# PSU_LM2704_16V5.net
KiCad netlist of a schematic drawn in Altium Designer
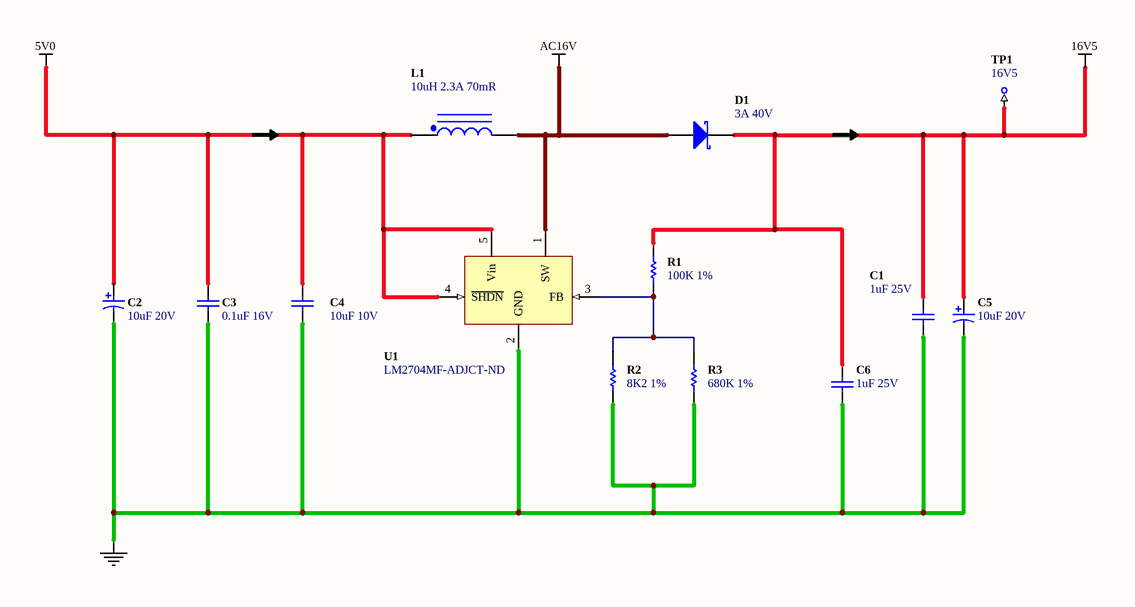
[diagram p0: PSU_LM2704_16V5.SchDoc]

(export (version "E")
  (design (tool "Eeschema 10.0.6"))
  (components
    (comp (ref "C1")
      (value "1uF 25V")
      (footprint "CAPC3216-STAR")
      (description "Capacitor, Ceramic, 1uF 10% 25V 1206 (3216) X7R")
      (fields (field (name "TOLERANCE") "10 %"))
      (libsource (lib "altium-import") (part "root_2_CAP-NP_"))
    )
    (comp (ref "C2")
      (value "10uF 20V")
      (footprint "CAPC3528-STAR")
      (description "Capacitor, Tantalum, 10uF 10% 20V MCCT-B (3528)")
      (fields (field (name "TOLERANCE") "10 %"))
      (libsource (lib "altium-import") (part "root_0_CAP-P_"))
    )
    (comp (ref "C3")
      (value "0.1uF 16V")
      (footprint "CAPC1005-STAR")
      (description "Capacitor, Ceramic, 0.1uF 10% 16V 0402 (1005) X7R")
      (fields (field (name "TOLERANCE") "10 %"))
      (libsource (lib "altium-import") (part "root_0_CAP-NP_"))
    )
    (comp (ref "C4")
      (value "10uF 10V")
      (footprint "CAPC2012-STAR")
      (description "Capacitor, Ceramic, 10uF 10% 10V 0805 (2012) X5R")
      (fields (field (name "TOLERANCE") "10 %"))
      (libsource (lib "altium-import") (part "root_2_CAP-NP_"))
    )
    (comp (ref "C5")
      (value "10uF 20V")
      (footprint "CAPC3528-STAR")
      (description "Capacitor, Tantalum, 10uF 10% 20V MCCT-B (3528)")
      (fields (field (name "TOLERANCE") "10 %"))
      (libsource (lib "altium-import") (part "root_0_CAP-P_"))
    )
    (comp (ref "C6")
      (value "1uF 25V")
      (footprint "CAPC3216-STAR")
      (description "Capacitor, Ceramic, 1uF 10% 25V 1206 (3216) X7R")
      (fields (field (name "TOLERANCE") "10 %"))
      (libsource (lib "altium-import") (part "root_2_CAP-NP_"))
    )
    (comp (ref "D1")
      (value "3A 40V")
      (footprint "DIOM5027")
      (description "Schottky Diode, 3A 40V")
      (libsource (lib "altium-import") (part "root_0_DIO-SCHOTTKY-1S_"))
    )
    (comp (ref "L1")
      (value "10uH 2.3A 70mR")
      (footprint "INDP7575")
      (description "Inductor, Magnetic Core 10uH 2.3A 70mR INDP7575")
      (libsource (lib "altium-import") (part "root_0_IND-IRON-DOT_"))
    )
    (comp (ref "R1")
      (value "100K 1%")
      (footprint "RESC1005-STAR")
      (description "Resistor, 100K 1% 0402 (1005)")
      (fields (field (name "TOLERANCE") "1 %"))
      (libsource (lib "altium-import") (part "root_2_RES_"))
    )
    (comp (ref "R2")
      (value "8K2 1%")
      (footprint "RESC1005-STAR")
      (description "Resistor, 8K2 1% 0402 (1005)")
      (fields (field (name "TOLERANCE") "1 %"))
      (libsource (lib "altium-import") (part "root_2_RES_"))
    )
    (comp (ref "R3")
      (value "680K 1%")
      (footprint "RESC1005-STAR")
      (description "Resistor, 680K 1% 0402 (1005)")
      (fields (field (name "TOLERANCE") "1 %"))
      (libsource (lib "altium-import") (part "root_2_RES_"))
    )
    (comp (ref "TP1")
      (value "16V5")
      (footprint "TestPin")
      (description "Test Point, PCB Mount with Silkscreen Box")
      (libsource (lib "AltiumDesignLibrary") (part "TestPin"))
    )
    (comp (ref "U1")
      (value "LM2704MF-ADJCT-ND")
      (footprint "SOT95P284-5")
      (libsource (lib "altium-import") (part "root_0_VRG-SW-5_"))
    )
  )
  (nets
    (net (code "1") (name "5V0") (class "Default")
      (node (ref "C2") (pin "1") (pinfunction "1_1") (pintype "passive"))
      (node (ref "C3") (pin "1") (pinfunction "1_1") (pintype "passive"))
      (node (ref "C4") (pin "2") (pinfunction "2_2") (pintype "passive"))
      (node (ref "L1") (pin "1") (pinfunction "1_1") (pintype "passive"))
      (node (ref "U1") (pin "4") (pinfunction "~{SHDN}_4") (pintype "input"))
      (node (ref "U1") (pin "5") (pinfunction "Vin_5") (pintype "power_in"))
    )
    (net (code "2") (name "16V5") (class "Default")
      (node (ref "C1") (pin "2") (pinfunction "2_2") (pintype "passive"))
      (node (ref "C5") (pin "1") (pinfunction "1_1") (pintype "passive"))
      (node (ref "C6") (pin "2") (pinfunction "2_2") (pintype "passive"))
      (node (ref "D1") (pin "2") (pinfunction "K_2") (pintype "passive"))
      (node (ref "R1") (pin "2") (pinfunction "2_2") (pintype "passive"))
      (node (ref "TP1") (pin "1") (pinfunction "1_1") (pintype "input"))
    )
    (net (code "3") (name "AC16V") (class "Default")
      (node (ref "D1") (pin "1") (pinfunction "A_1") (pintype "passive"))
      (node (ref "L1") (pin "2") (pinfunction "2_2") (pintype "passive"))
      (node (ref "U1") (pin "1") (pinfunction "SW_1") (pintype "open_collector"))
    )
    (net (code "4") (name "GND") (class "Default")
      (node (ref "C1") (pin "1") (pinfunction "1_1") (pintype "passive"))
      (node (ref "C2") (pin "2") (pinfunction "2_2") (pintype "passive"))
      (node (ref "C3") (pin "2") (pinfunction "2_2") (pintype "passive"))
      (node (ref "C4") (pin "1") (pinfunction "1_1") (pintype "passive"))
      (node (ref "C5") (pin "2") (pinfunction "2_2") (pintype "passive"))
      (node (ref "C6") (pin "1") (pinfunction "1_1") (pintype "passive"))
      (node (ref "R2") (pin "1") (pinfunction "1_1") (pintype "passive"))
      (node (ref "R3") (pin "1") (pinfunction "1_1") (pintype "passive"))
      (node (ref "U1") (pin "2") (pinfunction "GND_2") (pintype "power_in"))
    )
    (net (code "5") (name "Net-(U1-FB)") (class "Default")
      (node (ref "R1") (pin "1") (pinfunction "1_1") (pintype "passive"))
      (node (ref "R2") (pin "2") (pinfunction "2_2") (pintype "passive"))
      (node (ref "R3") (pin "2") (pinfunction "2_2") (pintype "passive"))
      (node (ref "U1") (pin "3") (pinfunction "FB_3") (pintype "input"))
    )
  )
)
